# Clock.net
KiCad netlist of a schematic drawn in Altium Designer
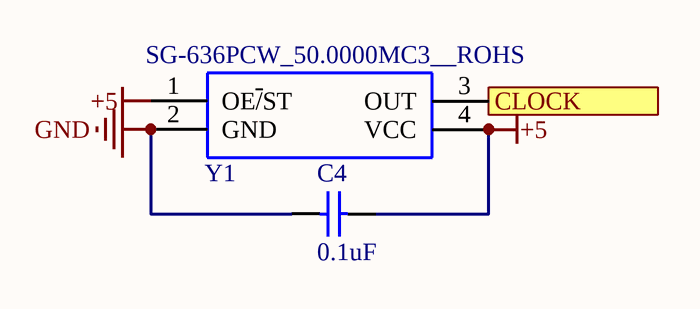
[diagram p0: Clock.SchDoc]

(export (version "E")
  (design (tool "Eeschema 10.0.6"))
  (components
    (comp (ref "C4")
      (value "0.1uF")
      (footprint "CAPC2013X94X50LL20T25")
      (description "Chip Capacitor, 0.1 uF, +/- 5%, 50 V, -55 to 125 degC, 0805 (2012 Metric), RoHS, Tape and Reel")
      (fields (field (name "TOLERANCE") "5%") (field (name "MANUFACTURER") "AVX"))
      (libsource (lib "Altium Content Vault") (part "CAP-NP-2"))
    )
    (comp (ref "Y1")
      (value "SG-636PCW_50.0000MC3__ROHS")
      (footprint "SG-636")
      (description "Standard Clock Oscillators 50MHz 3.3Volt 100ppm -20C +70C")
      (fields (field (name "MANUFACTURER_PART_NUMBER") "SG-636PCW 50.0000MC3: ROHS"))
      (libsource (lib "Husky Robotics Standard Library 2019-2020") (part "SG-636"))
    )
  )
  (nets
    (net (code "1") (name "+5") (class "Default")
      (node (ref "C4") (pin "1") (pinfunction "1_1") (pintype "passive"))
      (node (ref "Y1") (pin "1") (pinfunction "OE~{/}ST_1") (pintype "passive"))
      (node (ref "Y1") (pin "4") (pinfunction "VCC_4") (pintype "power_in"))
    )
    (net (code "2") (name "/CLOCK") (class "Default")
      (node (ref "Y1") (pin "3") (pinfunction "OUT_3") (pintype "passive"))
    )
    (net (code "3") (name "GND") (class "Default")
      (node (ref "C4") (pin "2") (pinfunction "2_2") (pintype "passive"))
      (node (ref "Y1") (pin "2") (pinfunction "GND_2") (pintype "passive"))
    )
  )
)
